# VRegulatorBoard.net
KiCad netlist of a schematic drawn in EAGLE
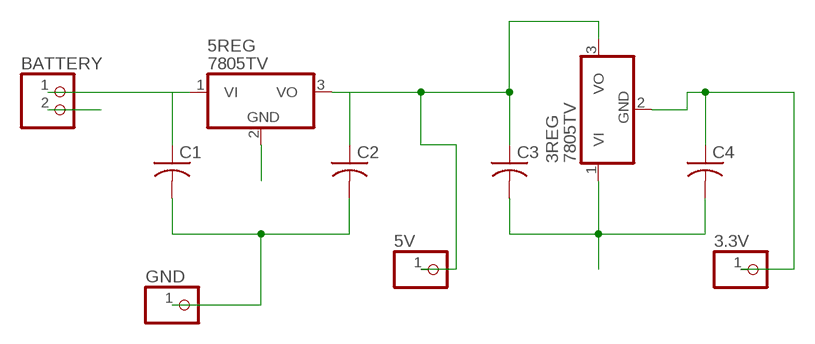
[diagram p0: schematic, sheet 1]

(export (version "E")
  (design (tool "Eeschema 10.0.6"))
  (components
    (comp (ref "3.3V")
      (value "PINHD-1X1")
      (footprint "eagle-import:1X01")
      (libsource (lib "eagle-import") (part "PINHD-1X1"))
    )
    (comp (ref "3REG")
      (value "7805TV")
      (footprint "eagle-import:TO220V")
      (libsource (lib "eagle-import") (part "78TV05"))
    )
    (comp (ref "5REG")
      (value "7805TV")
      (footprint "eagle-import:TO220V")
      (libsource (lib "eagle-import") (part "78TV05"))
    )
    (comp (ref "5V")
      (value "PINHD-1X1")
      (footprint "eagle-import:1X01")
      (libsource (lib "eagle-import") (part "PINHD-1X1"))
    )
    (comp (ref "BATTERY")
      (value "PINHD-1X2")
      (footprint "eagle-import:1X02")
      (libsource (lib "eagle-import") (part "PINHD-1X2"))
    )
    (comp (ref "C1")
      (value "C-US050-025X075")
      (footprint "eagle-import:C050-025X075")
      (libsource (lib "eagle-import") (part "C-US050-025X075"))
    )
    (comp (ref "C2")
      (value "C-US050-025X075")
      (footprint "eagle-import:C050-025X075")
      (libsource (lib "eagle-import") (part "C-US050-025X075"))
    )
    (comp (ref "C3")
      (value "C-US050-025X075")
      (footprint "eagle-import:C050-025X075")
      (libsource (lib "eagle-import") (part "C-US050-025X075"))
    )
    (comp (ref "C4")
      (value "C-US050-025X075")
      (footprint "eagle-import:C050-025X075")
      (libsource (lib "eagle-import") (part "C-US050-025X075"))
    )
    (comp (ref "GND")
      (value "PINHD-1X1")
      (footprint "eagle-import:1X01")
      (libsource (lib "eagle-import") (part "PINHD-1X1"))
    )
  )
  (nets
    (net (code "1") (name "/GND") (class "Default")
      (node (ref "3REG") (pin "1") (pinfunction "VI_1") (pintype "input"))
      (node (ref "5REG") (pin "2") (pinfunction "GND_2") (pintype "passive"))
      (node (ref "BATTERY") (pin "2") (pinfunction "2_2") (pintype "passive"))
      (node (ref "C1") (pin "2") (pinfunction "2_2") (pintype "passive"))
      (node (ref "C2") (pin "2") (pinfunction "2_2") (pintype "passive"))
      (node (ref "C3") (pin "2") (pinfunction "2_2") (pintype "passive"))
      (node (ref "C4") (pin "2") (pinfunction "2_2") (pintype "passive"))
      (node (ref "GND") (pin "1") (pinfunction "1_1") (pintype "passive"))
    )
    (net (code "2") (name "Net-(3REG-GND)") (class "Default")
      (node (ref "3.3V") (pin "1") (pinfunction "1_1") (pintype "passive"))
      (node (ref "3REG") (pin "2") (pinfunction "GND_2") (pintype "passive"))
      (node (ref "C4") (pin "1") (pinfunction "1_1") (pintype "passive"))
    )
    (net (code "3") (name "Net-(3REG-VO)") (class "Default")
      (node (ref "3REG") (pin "3") (pinfunction "VO_3") (pintype "passive"))
      (node (ref "5REG") (pin "3") (pinfunction "VO_3") (pintype "passive"))
      (node (ref "5V") (pin "1") (pinfunction "1_1") (pintype "passive"))
      (node (ref "C2") (pin "1") (pinfunction "1_1") (pintype "passive"))
      (node (ref "C3") (pin "1") (pinfunction "1_1") (pintype "passive"))
    )
    (net (code "4") (name "Net-(5REG-VI)") (class "Default")
      (node (ref "5REG") (pin "1") (pinfunction "VI_1") (pintype "input"))
      (node (ref "BATTERY") (pin "1") (pinfunction "1_1") (pintype "passive"))
      (node (ref "C1") (pin "1") (pinfunction "1_1") (pintype "passive"))
    )
  )
)
